# Sidekick-v02.net
KiCad netlist of a schematic drawn in EAGLE
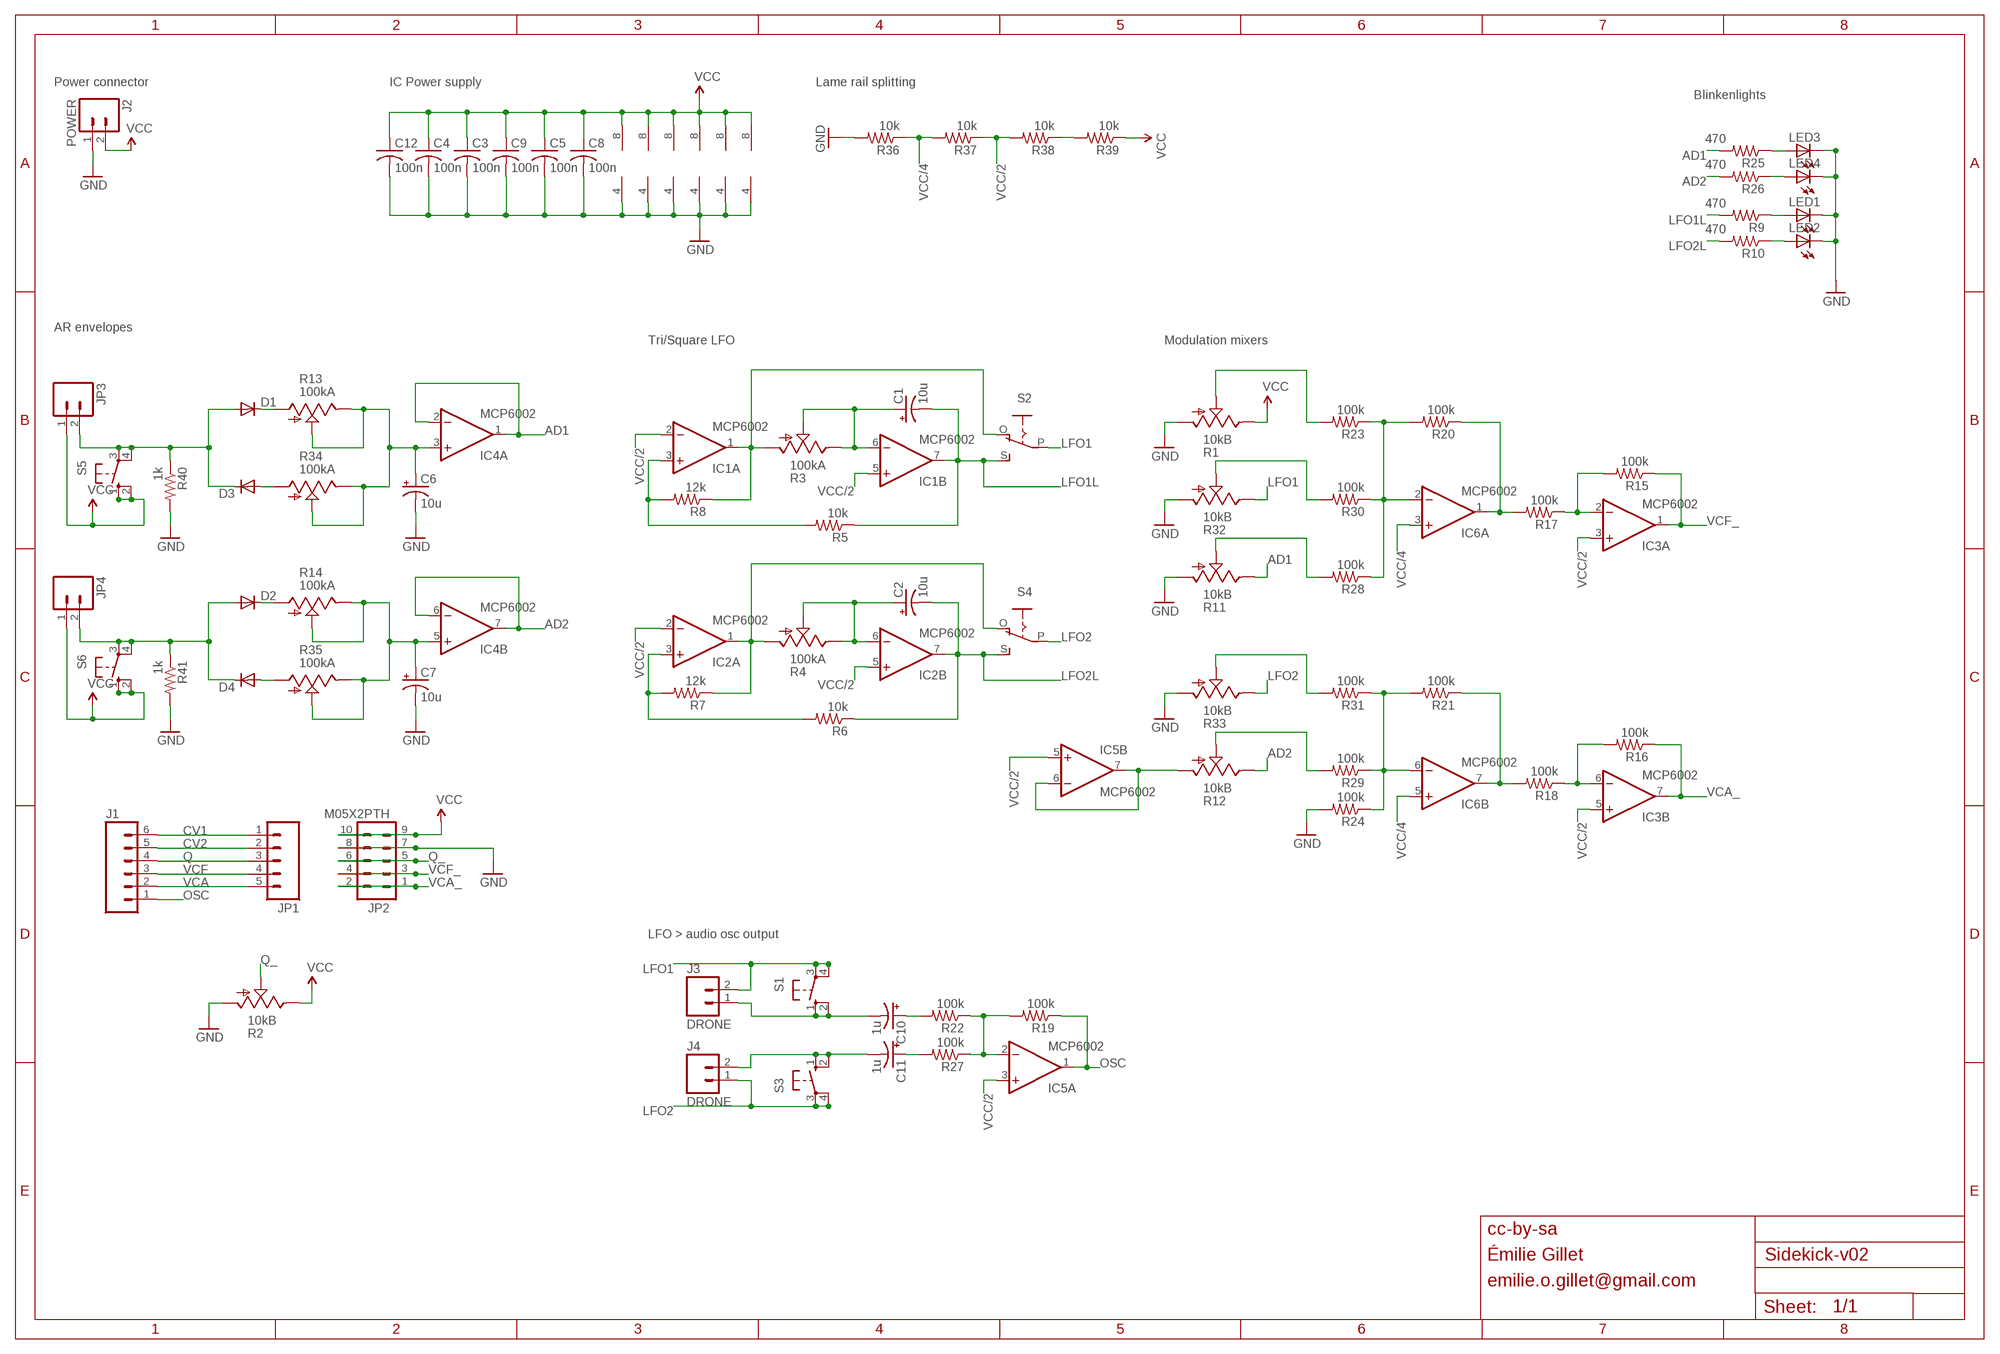
[diagram p0: schematic, sheet 1]

(export (version "E")
  (design (tool "Eeschema 10.0.6"))
  (components
    (comp (ref "C1")
      (value "10u")
      (footprint "eagle-import:E2,5-6")
      (libsource (lib "eagle-import") (part "CPOL-USE2.5-6"))
    )
    (comp (ref "C2")
      (value "10u")
      (footprint "eagle-import:E2,5-6")
      (libsource (lib "eagle-import") (part "CPOL-USE2.5-6"))
    )
    (comp (ref "C3")
      (value "100n")
      (footprint "eagle-import:C025-024X044")
      (libsource (lib "eagle-import") (part "C-US025-024X044"))
    )
    (comp (ref "C4")
      (value "100n")
      (footprint "eagle-import:C025-024X044")
      (libsource (lib "eagle-import") (part "C-US025-024X044"))
    )
    (comp (ref "C5")
      (value "100n")
      (footprint "eagle-import:C025-024X044")
      (libsource (lib "eagle-import") (part "C-US025-024X044"))
    )
    (comp (ref "C6")
      (value "10u")
      (footprint "eagle-import:E2,5-6")
      (libsource (lib "eagle-import") (part "CPOL-USE2.5-6"))
    )
    (comp (ref "C7")
      (value "10u")
      (footprint "eagle-import:E2,5-6")
      (libsource (lib "eagle-import") (part "CPOL-USE2.5-6"))
    )
    (comp (ref "C8")
      (value "100n")
      (footprint "eagle-import:C025-024X044")
      (libsource (lib "eagle-import") (part "C-US025-024X044"))
    )
    (comp (ref "C9")
      (value "100n")
      (footprint "eagle-import:C025-024X044")
      (libsource (lib "eagle-import") (part "C-US025-024X044"))
    )
    (comp (ref "C10")
      (value "1u")
      (footprint "eagle-import:E2,5-6")
      (libsource (lib "eagle-import") (part "CPOL-USE2.5-6"))
    )
    (comp (ref "C11")
      (value "1u")
      (footprint "eagle-import:E2,5-6")
      (libsource (lib "eagle-import") (part "CPOL-USE2.5-6"))
    )
    (comp (ref "C12")
      (value "100n")
      (footprint "eagle-import:C025-024X044")
      (libsource (lib "eagle-import") (part "C-US025-024X044"))
    )
    (comp (ref "D1")
      (value "DIODE-D-5")
      (footprint "eagle-import:D-5")
      (libsource (lib "eagle-import") (part "DIODE-D-5"))
    )
    (comp (ref "D2")
      (value "DIODE-D-5")
      (footprint "eagle-import:D-5")
      (libsource (lib "eagle-import") (part "DIODE-D-5"))
    )
    (comp (ref "D3")
      (value "DIODE-D-5")
      (footprint "eagle-import:D-5")
      (libsource (lib "eagle-import") (part "DIODE-D-5"))
    )
    (comp (ref "D4")
      (value "DIODE-D-5")
      (footprint "eagle-import:D-5")
      (libsource (lib "eagle-import") (part "DIODE-D-5"))
    )
    (comp (ref "IC1")
      (value "MCP6002")
      (footprint "eagle-import:DIL08")
      (libsource (lib "eagle-import") (part "TL082P"))
    )
    (comp (ref "IC2")
      (value "MCP6002")
      (footprint "eagle-import:DIL08")
      (libsource (lib "eagle-import") (part "TL082P"))
    )
    (comp (ref "IC3")
      (value "MCP6002")
      (footprint "eagle-import:DIL08")
      (libsource (lib "eagle-import") (part "TL082P"))
    )
    (comp (ref "IC4")
      (value "MCP6002")
      (footprint "eagle-import:DIL08")
      (libsource (lib "eagle-import") (part "TL082P"))
    )
    (comp (ref "IC5")
      (value "MCP6002")
      (footprint "eagle-import:DIL08")
      (libsource (lib "eagle-import") (part "TL082P"))
    )
    (comp (ref "IC6")
      (value "MCP6002")
      (footprint "eagle-import:DIL08")
      (libsource (lib "eagle-import") (part "TL082P"))
    )
    (comp (ref "J1")
      (value "M06SIP")
      (footprint "eagle-import:1X06")
      (libsource (lib "eagle-import") (part "M06SIP"))
    )
    (comp (ref "J2")
      (value "POWER")
      (footprint "eagle-import:1X02")
      (libsource (lib "eagle-import") (part "M02PTH"))
    )
    (comp (ref "J3")
      (value "DRONE")
      (footprint "eagle-import:1X02")
      (libsource (lib "eagle-import") (part "M02PTH"))
    )
    (comp (ref "J4")
      (value "DRONE")
      (footprint "eagle-import:1X02")
      (libsource (lib "eagle-import") (part "M02PTH"))
    )
    (comp (ref "JP1")
      (value "M05PTH")
      (footprint "eagle-import:1X05")
      (libsource (lib "eagle-import") (part "M05PTH"))
    )
    (comp (ref "JP2")
      (value "M05X2PTH")
      (footprint "eagle-import:AVR_ICSP")
      (libsource (lib "eagle-import") (part "M05X2PTH"))
    )
    (comp (ref "JP3")
      (value "M02")
      (footprint "eagle-import:1X02_LONGPADS")
      (libsource (lib "eagle-import") (part "M02"))
    )
    (comp (ref "JP4")
      (value "M02")
      (footprint "eagle-import:1X02_LONGPADS")
      (libsource (lib "eagle-import") (part "M02"))
    )
    (comp (ref "LED1")
      (value "LED3MM")
      (footprint "eagle-import:LED3MM")
      (libsource (lib "eagle-import") (part "LED3MM"))
    )
    (comp (ref "LED2")
      (value "LED3MM")
      (footprint "eagle-import:LED3MM")
      (libsource (lib "eagle-import") (part "LED3MM"))
    )
    (comp (ref "LED3")
      (value "LED3MM")
      (footprint "eagle-import:LED3MM")
      (libsource (lib "eagle-import") (part "LED3MM"))
    )
    (comp (ref "LED4")
      (value "LED3MM")
      (footprint "eagle-import:LED3MM")
      (libsource (lib "eagle-import") (part "LED3MM"))
    )
    (comp (ref "R1")
      (value "10kB")
      (footprint "eagle-import:ALPS_POT_SFE")
      (libsource (lib "eagle-import") (part "POT_US"))
    )
    (comp (ref "R2")
      (value "10kB")
      (footprint "eagle-import:ALPS_POT_SFE")
      (libsource (lib "eagle-import") (part "POT_US"))
    )
    (comp (ref "R3")
      (value "100kA")
      (footprint "eagle-import:ALPS_POT_SFE")
      (libsource (lib "eagle-import") (part "POT_US"))
    )
    (comp (ref "R4")
      (value "100kA")
      (footprint "eagle-import:ALPS_POT_SFE")
      (libsource (lib "eagle-import") (part "POT_US"))
    )
    (comp (ref "R5")
      (value "10k")
      (footprint "eagle-import:0204_7")
      (libsource (lib "eagle-import") (part "R-US_0204/7"))
    )
    (comp (ref "R6")
      (value "10k")
      (footprint "eagle-import:0204_7")
      (libsource (lib "eagle-import") (part "R-US_0204/7"))
    )
    (comp (ref "R7")
      (value "12k")
      (footprint "eagle-import:0204_7")
      (libsource (lib "eagle-import") (part "R-US_0204/7"))
    )
    (comp (ref "R8")
      (value "12k")
      (footprint "eagle-import:0204_7")
      (libsource (lib "eagle-import") (part "R-US_0204/7"))
    )
    (comp (ref "R9")
      (value "470")
      (footprint "eagle-import:0204_7")
      (libsource (lib "eagle-import") (part "R-US_0204/7"))
    )
    (comp (ref "R10")
      (value "470")
      (footprint "eagle-import:0204_7")
      (libsource (lib "eagle-import") (part "R-US_0204/7"))
    )
    (comp (ref "R11")
      (value "10kB")
      (footprint "eagle-import:ALPS_POT_SFE")
      (libsource (lib "eagle-import") (part "POT_US"))
    )
    (comp (ref "R12")
      (value "10kB")
      (footprint "eagle-import:ALPS_POT_SFE")
      (libsource (lib "eagle-import") (part "POT_US"))
    )
    (comp (ref "R13")
      (value "100kA")
      (footprint "eagle-import:ALPS_POT_SFE")
      (libsource (lib "eagle-import") (part "POT_US"))
    )
    (comp (ref "R14")
      (value "100kA")
      (footprint "eagle-import:ALPS_POT_SFE")
      (libsource (lib "eagle-import") (part "POT_US"))
    )
    (comp (ref "R15")
      (value "100k")
      (footprint "eagle-import:0204_7")
      (libsource (lib "eagle-import") (part "R-US_0204/7"))
    )
    (comp (ref "R16")
      (value "100k")
      (footprint "eagle-import:0204_7")
      (libsource (lib "eagle-import") (part "R-US_0204/7"))
    )
    (comp (ref "R17")
      (value "100k")
      (footprint "eagle-import:0204_7")
      (libsource (lib "eagle-import") (part "R-US_0204/7"))
    )
    (comp (ref "R18")
      (value "100k")
      (footprint "eagle-import:0204_7")
      (libsource (lib "eagle-import") (part "R-US_0204/7"))
    )
    (comp (ref "R19")
      (value "100k")
      (footprint "eagle-import:0204_7")
      (libsource (lib "eagle-import") (part "R-US_0204/7"))
    )
    (comp (ref "R20")
      (value "100k")
      (footprint "eagle-import:0204_7")
      (libsource (lib "eagle-import") (part "R-US_0204/7"))
    )
    (comp (ref "R21")
      (value "100k")
      (footprint "eagle-import:0204_7")
      (libsource (lib "eagle-import") (part "R-US_0204/7"))
    )
    (comp (ref "R22")
      (value "100k")
      (footprint "eagle-import:0204_7")
      (libsource (lib "eagle-import") (part "R-US_0204/7"))
    )
    (comp (ref "R23")
      (value "100k")
      (footprint "eagle-import:0204_7")
      (libsource (lib "eagle-import") (part "R-US_0204/7"))
    )
    (comp (ref "R24")
      (value "100k")
      (footprint "eagle-import:0204_7")
      (libsource (lib "eagle-import") (part "R-US_0204/7"))
    )
    (comp (ref "R25")
      (value "470")
      (footprint "eagle-import:0204_7")
      (libsource (lib "eagle-import") (part "R-US_0204/7"))
    )
    (comp (ref "R26")
      (value "470")
      (footprint "eagle-import:0204_7")
      (libsource (lib "eagle-import") (part "R-US_0204/7"))
    )
    (comp (ref "R27")
      (value "100k")
      (footprint "eagle-import:0204_7")
      (libsource (lib "eagle-import") (part "R-US_0204/7"))
    )
    (comp (ref "R28")
      (value "100k")
      (footprint "eagle-import:0204_7")
      (libsource (lib "eagle-import") (part "R-US_0204/7"))
    )
    (comp (ref "R29")
      (value "100k")
      (footprint "eagle-import:0204_7")
      (libsource (lib "eagle-import") (part "R-US_0204/7"))
    )
    (comp (ref "R30")
      (value "100k")
      (footprint "eagle-import:0204_7")
      (libsource (lib "eagle-import") (part "R-US_0204/7"))
    )
    (comp (ref "R31")
      (value "100k")
      (footprint "eagle-import:0204_7")
      (libsource (lib "eagle-import") (part "R-US_0204/7"))
    )
    (comp (ref "R32")
      (value "10kB")
      (footprint "eagle-import:ALPS_POT_SFE")
      (libsource (lib "eagle-import") (part "POT_US"))
    )
    (comp (ref "R33")
      (value "10kB")
      (footprint "eagle-import:ALPS_POT_SFE")
      (libsource (lib "eagle-import") (part "POT_US"))
    )
    (comp (ref "R34")
      (value "100kA")
      (footprint "eagle-import:ALPS_POT_SFE")
      (libsource (lib "eagle-import") (part "POT_US"))
    )
    (comp (ref "R35")
      (value "100kA")
      (footprint "eagle-import:ALPS_POT_SFE")
      (libsource (lib "eagle-import") (part "POT_US"))
    )
    (comp (ref "R36")
      (value "10k")
      (footprint "eagle-import:0204_7")
      (libsource (lib "eagle-import") (part "R-US_0204/7"))
    )
    (comp (ref "R37")
      (value "10k")
      (footprint "eagle-import:0204_7")
      (libsource (lib "eagle-import") (part "R-US_0204/7"))
    )
    (comp (ref "R38")
      (value "10k")
      (footprint "eagle-import:0204_7")
      (libsource (lib "eagle-import") (part "R-US_0204/7"))
    )
    (comp (ref "R39")
      (value "10k")
      (footprint "eagle-import:0204_7")
      (libsource (lib "eagle-import") (part "R-US_0204/7"))
    )
    (comp (ref "R40")
      (value "1k")
      (footprint "eagle-import:0204_7")
      (libsource (lib "eagle-import") (part "R-US_0204/7"))
    )
    (comp (ref "R41")
      (value "1k")
      (footprint "eagle-import:0204_7")
      (libsource (lib "eagle-import") (part "R-US_0204/7"))
    )
    (comp (ref "S1")
      (value "40-XX")
      (footprint "eagle-import:B3F-40XX")
      (libsource (lib "eagle-import") (part "40-XX"))
    )
    (comp (ref "S2")
      (value "EG1218S")
      (footprint "eagle-import:EG1218")
      (libsource (lib "eagle-import") (part "EG1218S"))
    )
    (comp (ref "S3")
      (value "40-XX")
      (footprint "eagle-import:B3F-40XX")
      (libsource (lib "eagle-import") (part "40-XX"))
    )
    (comp (ref "S4")
      (value "EG1218S")
      (footprint "eagle-import:EG1218")
      (libsource (lib "eagle-import") (part "EG1218S"))
    )
    (comp (ref "S5")
      (value "40-XX")
      (footprint "eagle-import:B3F-40XX")
      (libsource (lib "eagle-import") (part "40-XX"))
    )
    (comp (ref "S6")
      (value "40-XX")
      (footprint "eagle-import:B3F-40XX")
      (libsource (lib "eagle-import") (part "40-XX"))
    )
  )
  (nets
    (net (code "1") (name "/AD1") (class "Default")
      (node (ref "IC4") (pin "1") (pinfunction "OUT_1") (pintype "output"))
      (node (ref "IC4") (pin "2") (pinfunction "-IN_2") (pintype "input"))
      (node (ref "R11") (pin "P$1") (pinfunction "E_P$1") (pintype "passive"))
      (node (ref "R25") (pin "2") (pinfunction "2_2") (pintype "passive"))
    )
    (net (code "2") (name "/AD2") (class "Default")
      (node (ref "IC4") (pin "6") (pinfunction "-IN_6") (pintype "input"))
      (node (ref "IC4") (pin "7") (pinfunction "OUT_7") (pintype "output"))
      (node (ref "R12") (pin "P$1") (pinfunction "E_P$1") (pintype "passive"))
      (node (ref "R26") (pin "2") (pinfunction "2_2") (pintype "passive"))
    )
    (net (code "3") (name "/CV1") (class "Default")
      (node (ref "J1") (pin "6") (pinfunction "6_6") (pintype "passive"))
      (node (ref "JP1") (pin "1") (pinfunction "1_1") (pintype "passive"))
    )
    (net (code "4") (name "/CV2") (class "Default")
      (node (ref "J1") (pin "5") (pinfunction "5_5") (pintype "passive"))
      (node (ref "JP1") (pin "2") (pinfunction "2_2") (pintype "passive"))
    )
    (net (code "5") (name "/LFO1") (class "Default")
      (node (ref "J3") (pin "2") (pinfunction "2_2") (pintype "passive"))
      (node (ref "R32") (pin "P$1") (pinfunction "E_P$1") (pintype "passive"))
      (node (ref "S1") (pin "3") (pinfunction "P_3") (pintype "passive"))
      (node (ref "S1") (pin "4") (pinfunction "P1_4") (pintype "passive"))
      (node (ref "S2") (pin "P") (pinfunction "P_P") (pintype "passive"))
    )
    (net (code "6") (name "/LFO1L") (class "Default")
      (node (ref "C1") (pin "-") (pinfunction "-_-") (pintype "passive"))
      (node (ref "IC1") (pin "7") (pinfunction "OUT_7") (pintype "output"))
      (node (ref "R5") (pin "1") (pinfunction "1_1") (pintype "passive"))
      (node (ref "R9") (pin "2") (pinfunction "2_2") (pintype "passive"))
      (node (ref "S2") (pin "S") (pinfunction "S_S") (pintype "passive"))
    )
    (net (code "7") (name "/LFO2") (class "Default")
      (node (ref "J4") (pin "1") (pinfunction "1_1") (pintype "passive"))
      (node (ref "R33") (pin "P$1") (pinfunction "E_P$1") (pintype "passive"))
      (node (ref "S3") (pin "3") (pinfunction "P_3") (pintype "passive"))
      (node (ref "S3") (pin "4") (pinfunction "P1_4") (pintype "passive"))
      (node (ref "S4") (pin "P") (pinfunction "P_P") (pintype "passive"))
    )
    (net (code "8") (name "/LFO2L") (class "Default")
      (node (ref "C2") (pin "-") (pinfunction "-_-") (pintype "passive"))
      (node (ref "IC2") (pin "7") (pinfunction "OUT_7") (pintype "output"))
      (node (ref "R10") (pin "2") (pinfunction "2_2") (pintype "passive"))
      (node (ref "R6") (pin "1") (pinfunction "1_1") (pintype "passive"))
      (node (ref "S4") (pin "S") (pinfunction "S_S") (pintype "passive"))
    )
    (net (code "9") (name "/OSC") (class "Default")
      (node (ref "IC5") (pin "1") (pinfunction "OUT_1") (pintype "output"))
      (node (ref "J1") (pin "1") (pinfunction "1_1") (pintype "passive"))
      (node (ref "R19") (pin "1") (pinfunction "1_1") (pintype "passive"))
    )
    (net (code "10") (name "/Q") (class "Default")
      (node (ref "J1") (pin "4") (pinfunction "4_4") (pintype "passive"))
      (node (ref "JP1") (pin "3") (pinfunction "3_3") (pintype "passive"))
    )
    (net (code "11") (name "/Q_") (class "Default")
      (node (ref "JP2") (pin "5") (pinfunction "5_5") (pintype "passive"))
      (node (ref "JP2") (pin "6") (pinfunction "6_6") (pintype "passive"))
      (node (ref "R2") (pin "P$2") (pinfunction "S_P$2") (pintype "passive"))
    )
    (net (code "12") (name "/VCA") (class "Default")
      (node (ref "J1") (pin "2") (pinfunction "2_2") (pintype "passive"))
      (node (ref "JP1") (pin "5") (pinfunction "5_5") (pintype "passive"))
    )
    (net (code "13") (name "/VCA_") (class "Default")
      (node (ref "IC3") (pin "7") (pinfunction "OUT_7") (pintype "output"))
      (node (ref "JP2") (pin "1") (pinfunction "1_1") (pintype "passive"))
      (node (ref "JP2") (pin "2") (pinfunction "2_2") (pintype "passive"))
      (node (ref "R16") (pin "1") (pinfunction "1_1") (pintype "passive"))
    )
    (net (code "14") (name "/VCC{slash}2") (class "Default")
      (node (ref "IC1") (pin "2") (pinfunction "-IN_2") (pintype "input"))
      (node (ref "IC1") (pin "5") (pinfunction "+IN_5") (pintype "input"))
      (node (ref "IC2") (pin "2") (pinfunction "-IN_2") (pintype "input"))
      (node (ref "IC2") (pin "5") (pinfunction "+IN_5") (pintype "input"))
      (node (ref "IC3") (pin "3") (pinfunction "+IN_3") (pintype "input"))
      (node (ref "IC3") (pin "5") (pinfunction "+IN_5") (pintype "input"))
      (node (ref "IC5") (pin "3") (pinfunction "+IN_3") (pintype "input"))
      (node (ref "IC5") (pin "5") (pinfunction "+IN_5") (pintype "input"))
      (node (ref "R37") (pin "1") (pinfunction "1_1") (pintype "passive"))
      (node (ref "R38") (pin "2") (pinfunction "2_2") (pintype "passive"))
    )
    (net (code "15") (name "/VCC{slash}4") (class "Default")
      (node (ref "IC6") (pin "3") (pinfunction "+IN_3") (pintype "input"))
      (node (ref "IC6") (pin "5") (pinfunction "+IN_5") (pintype "input"))
      (node (ref "R36") (pin "1") (pinfunction "1_1") (pintype "passive"))
      (node (ref "R37") (pin "2") (pinfunction "2_2") (pintype "passive"))
    )
    (net (code "16") (name "/VCF") (class "Default")
      (node (ref "J1") (pin "3") (pinfunction "3_3") (pintype "passive"))
      (node (ref "JP1") (pin "4") (pinfunction "4_4") (pintype "passive"))
    )
    (net (code "17") (name "/VCF_") (class "Default")
      (node (ref "IC3") (pin "1") (pinfunction "OUT_1") (pintype "output"))
      (node (ref "JP2") (pin "3") (pinfunction "3_3") (pintype "passive"))
      (node (ref "JP2") (pin "4") (pinfunction "4_4") (pintype "passive"))
      (node (ref "R15") (pin "1") (pinfunction "1_1") (pintype "passive"))
    )
    (net (code "18") (name "GND") (class "Default")
      (node (ref "C12") (pin "2") (pinfunction "2_2") (pintype "passive"))
      (node (ref "C3") (pin "2") (pinfunction "2_2") (pintype "passive"))
      (node (ref "C4") (pin "2") (pinfunction "2_2") (pintype "passive"))
      (node (ref "C5") (pin "2") (pinfunction "2_2") (pintype "passive"))
      (node (ref "C6") (pin "-") (pinfunction "-_-") (pintype "passive"))
      (node (ref "C7") (pin "-") (pinfunction "-_-") (pintype "passive"))
      (node (ref "C8") (pin "2") (pinfunction "2_2") (pintype "passive"))
      (node (ref "C9") (pin "2") (pinfunction "2_2") (pintype "passive"))
      (node (ref "IC1") (pin "4") (pinfunction "V-_4") (pintype "power_in"))
      (node (ref "IC2") (pin "4") (pinfunction "V-_4") (pintype "power_in"))
      (node (ref "IC3") (pin "4") (pinfunction "V-_4") (pintype "power_in"))
      (node (ref "IC4") (pin "4") (pinfunction "V-_4") (pintype "power_in"))
      (node (ref "IC5") (pin "4") (pinfunction "V-_4") (pintype "power_in"))
      (node (ref "IC6") (pin "4") (pinfunction "V-_4") (pintype "power_in"))
      (node (ref "J2") (pin "1") (pinfunction "1_1") (pintype "passive"))
      (node (ref "JP2") (pin "7") (pinfunction "7_7") (pintype "passive"))
      (node (ref "JP2") (pin "8") (pinfunction "8_8") (pintype "passive"))
      (node (ref "LED1") (pin "K") (pinfunction "C_K") (pintype "passive"))
      (node (ref "LED2") (pin "K") (pinfunction "C_K") (pintype "passive"))
      (node (ref "LED3") (pin "K") (pinfunction "C_K") (pintype "passive"))
      (node (ref "LED4") (pin "K") (pinfunction "C_K") (pintype "passive"))
      (node (ref "R1") (pin "P$3") (pinfunction "A_P$3") (pintype "passive"))
      (node (ref "R11") (pin "P$3") (pinfunction "A_P$3") (pintype "passive"))
      (node (ref "R2") (pin "P$3") (pinfunction "A_P$3") (pintype "passive"))
      (node (ref "R24") (pin "2") (pinfunction "2_2") (pintype "passive"))
      (node (ref "R32") (pin "P$3") (pinfunction "A_P$3") (pintype "passive"))
      (node (ref "R33") (pin "P$3") (pinfunction "A_P$3") (pintype "passive"))
      (node (ref "R36") (pin "2") (pinfunction "2_2") (pintype "passive"))
      (node (ref "R40") (pin "2") (pinfunction "2_2") (pintype "passive"))
      (node (ref "R41") (pin "2") (pinfunction "2_2") (pintype "passive"))
    )
    (net (code "19") (name "Net-(C10-Pad+)") (class "Default")
      (node (ref "C10") (pin "+") (pinfunction "+_+") (pintype "passive"))
      (node (ref "R22") (pin "2") (pinfunction "2_2") (pintype "passive"))
    )
    (net (code "20") (name "Net-(C11-Pad+)") (class "Default")
      (node (ref "C11") (pin "+") (pinfunction "+_+") (pintype "passive"))
      (node (ref "R27") (pin "2") (pinfunction "2_2") (pintype "passive"))
    )
    (net (code "21") (name "Net-(IC1A-+IN)") (class "Default")
      (node (ref "IC1") (pin "3") (pinfunction "+IN_3") (pintype "input"))
      (node (ref "R5") (pin "2") (pinfunction "2_2") (pintype "passive"))
      (node (ref "R8") (pin "2") (pinfunction "2_2") (pintype "passive"))
    )
    (net (code "22") (name "Net-(IC1A-OUT)") (class "Default")
      (node (ref "IC1") (pin "1") (pinfunction "OUT_1") (pintype "output"))
      (node (ref "R3") (pin "P$3") (pinfunction "A_P$3") (pintype "passive"))
      (node (ref "R8") (pin "1") (pinfunction "1_1") (pintype "passive"))
      (node (ref "S2") (pin "O") (pinfunction "O_O") (pintype "passive"))
    )
    (net (code "23") (name "Net-(IC1B--IN)") (class "Default")
      (node (ref "C1") (pin "+") (pinfunction "+_+") (pintype "passive"))
      (node (ref "IC1") (pin "6") (pinfunction "-IN_6") (pintype "input"))
      (node (ref "R3") (pin "P$1") (pinfunction "E_P$1") (pintype "passive"))
      (node (ref "R3") (pin "P$2") (pinfunction "S_P$2") (pintype "passive"))
    )
    (net (code "24") (name "Net-(IC2A-+IN)") (class "Default")
      (node (ref "IC2") (pin "3") (pinfunction "+IN_3") (pintype "input"))
      (node (ref "R6") (pin "2") (pinfunction "2_2") (pintype "passive"))
      (node (ref "R7") (pin "2") (pinfunction "2_2") (pintype "passive"))
    )
    (net (code "25") (name "Net-(IC2A-OUT)") (class "Default")
      (node (ref "IC2") (pin "1") (pinfunction "OUT_1") (pintype "output"))
      (node (ref "R4") (pin "P$3") (pinfunction "A_P$3") (pintype "passive"))
      (node (ref "R7") (pin "1") (pinfunction "1_1") (pintype "passive"))
      (node (ref "S4") (pin "O") (pinfunction "O_O") (pintype "passive"))
    )
    (net (code "26") (name "Net-(IC2B--IN)") (class "Default")
      (node (ref "C2") (pin "+") (pinfunction "+_+") (pintype "passive"))
      (node (ref "IC2") (pin "6") (pinfunction "-IN_6") (pintype "input"))
      (node (ref "R4") (pin "P$1") (pinfunction "E_P$1") (pintype "passive"))
      (node (ref "R4") (pin "P$2") (pinfunction "S_P$2") (pintype "passive"))
    )
    (net (code "27") (name "Net-(IC3A--IN)") (class "Default")
      (node (ref "IC3") (pin "2") (pinfunction "-IN_2") (pintype "input"))
      (node (ref "R15") (pin "2") (pinfunction "2_2") (pintype "passive"))
      (node (ref "R17") (pin "1") (pinfunction "1_1") (pintype "passive"))
    )
    (net (code "28") (name "Net-(IC3B--IN)") (class "Default")
      (node (ref "IC3") (pin "6") (pinfunction "-IN_6") (pintype "input"))
      (node (ref "R16") (pin "2") (pinfunction "2_2") (pintype "passive"))
      (node (ref "R18") (pin "1") (pinfunction "1_1") (pintype "passive"))
    )
    (net (code "29") (name "Net-(IC4A-+IN)") (class "Default")
      (node (ref "C6") (pin "+") (pinfunction "+_+") (pintype "passive"))
      (node (ref "IC4") (pin "3") (pinfunction "+IN_3") (pintype "input"))
      (node (ref "R13") (pin "P$1") (pinfunction "E_P$1") (pintype "passive"))
      (node (ref "R13") (pin "P$2") (pinfunction "S_P$2") (pintype "passive"))
      (node (ref "R34") (pin "P$1") (pinfunction "E_P$1") (pintype "passive"))
      (node (ref "R34") (pin "P$2") (pinfunction "S_P$2") (pintype "passive"))
    )
    (net (code "30") (name "Net-(IC4B-+IN)") (class "Default")
      (node (ref "C7") (pin "+") (pinfunction "+_+") (pintype "passive"))
      (node (ref "IC4") (pin "5") (pinfunction "+IN_5") (pintype "input"))
      (node (ref "R14") (pin "P$1") (pinfunction "E_P$1") (pintype "passive"))
      (node (ref "R14") (pin "P$2") (pinfunction "S_P$2") (pintype "passive"))
      (node (ref "R35") (pin "P$1") (pinfunction "E_P$1") (pintype "passive"))
      (node (ref "R35") (pin "P$2") (pinfunction "S_P$2") (pintype "passive"))
    )
    (net (code "31") (name "Net-(IC5A--IN)") (class "Default")
      (node (ref "IC5") (pin "2") (pinfunction "-IN_2") (pintype "input"))
      (node (ref "R19") (pin "2") (pinfunction "2_2") (pintype "passive"))
      (node (ref "R22") (pin "1") (pinfunction "1_1") (pintype "passive"))
      (node (ref "R27") (pin "1") (pinfunction "1_1") (pintype "passive"))
    )
    (net (code "32") (name "Net-(IC5B--IN)") (class "Default")
      (node (ref "IC5") (pin "6") (pinfunction "-IN_6") (pintype "input"))
      (node (ref "IC5") (pin "7") (pinfunction "OUT_7") (pintype "output"))
      (node (ref "R12") (pin "P$3") (pinfunction "A_P$3") (pintype "passive"))
    )
    (net (code "33") (name "Net-(IC6A--IN)") (class "Default")
      (node (ref "IC6") (pin "2") (pinfunction "-IN_2") (pintype "input"))
      (node (ref "R20") (pin "2") (pinfunction "2_2") (pintype "passive"))
      (node (ref "R23") (pin "1") (pinfunction "1_1") (pintype "passive"))
      (node (ref "R28") (pin "1") (pinfunction "1_1") (pintype "passive"))
      (node (ref "R30") (pin "1") (pinfunction "1_1") (pintype "passive"))
    )
    (net (code "34") (name "Net-(IC6A-OUT)") (class "Default")
      (node (ref "IC6") (pin "1") (pinfunction "OUT_1") (pintype "output"))
      (node (ref "R17") (pin "2") (pinfunction "2_2") (pintype "passive"))
      (node (ref "R20") (pin "1") (pinfunction "1_1") (pintype "passive"))
    )
    (net (code "35") (name "Net-(IC6B--IN)") (class "Default")
      (node (ref "IC6") (pin "6") (pinfunction "-IN_6") (pintype "input"))
      (node (ref "R21") (pin "2") (pinfunction "2_2") (pintype "passive"))
      (node (ref "R24") (pin "1") (pinfunction "1_1") (pintype "passive"))
      (node (ref "R29") (pin "1") (pinfunction "1_1") (pintype "passive"))
      (node (ref "R31") (pin "1") (pinfunction "1_1") (pintype "passive"))
    )
    (net (code "36") (name "Net-(IC6B-OUT)") (class "Default")
      (node (ref "IC6") (pin "7") (pinfunction "OUT_7") (pintype "output"))
      (node (ref "R18") (pin "2") (pinfunction "2_2") (pintype "passive"))
      (node (ref "R21") (pin "1") (pinfunction "1_1") (pintype "passive"))
    )
    (net (code "37") (name "Net-(LED1-PadA)") (class "Default")
      (node (ref "LED1") (pin "A") (pinfunction "A_A") (pintype "passive"))
      (node (ref "R9") (pin "1") (pinfunction "1_1") (pintype "passive"))
    )
    (net (code "38") (name "Net-(LED2-PadA)") (class "Default")
      (node (ref "LED2") (pin "A") (pinfunction "A_A") (pintype "passive"))
      (node (ref "R10") (pin "1") (pinfunction "1_1") (pintype "passive"))
    )
    (net (code "39") (name "Net-(LED3-PadA)") (class "Default")
      (node (ref "LED3") (pin "A") (pinfunction "A_A") (pintype "passive"))
      (node (ref "R25") (pin "1") (pinfunction "1_1") (pintype "passive"))
    )
    (net (code "40") (name "Net-(LED4-PadA)") (class "Default")
      (node (ref "LED4") (pin "A") (pinfunction "A_A") (pintype "passive"))
      (node (ref "R26") (pin "1") (pinfunction "1_1") (pintype "passive"))
    )
    (net (code "41") (name "Net-(R1-S)") (class "Default")
      (node (ref "R1") (pin "P$2") (pinfunction "S_P$2") (pintype "passive"))
      (node (ref "R23") (pin "2") (pinfunction "2_2") (pintype "passive"))
    )
    (net (code "42") (name "Net-(R11-S)") (class "Default")
      (node (ref "R11") (pin "P$2") (pinfunction "S_P$2") (pintype "passive"))
      (node (ref "R28") (pin "2") (pinfunction "2_2") (pintype "passive"))
    )
    (net (code "43") (name "Net-(R12-S)") (class "Default")
      (node (ref "R12") (pin "P$2") (pinfunction "S_P$2") (pintype "passive"))
      (node (ref "R29") (pin "2") (pinfunction "2_2") (pintype "passive"))
    )
    (net (code "44") (name "Net-(R13-A)") (class "Default")
      (node (ref "D1") (pin "C") (pinfunction "C_C") (pintype "passive"))
      (node (ref "R13") (pin "P$3") (pinfunction "A_P$3") (pintype "passive"))
    )
    (net (code "45") (name "Net-(R14-A)") (class "Default")
      (node (ref "D2") (pin "C") (pinfunction "C_C") (pintype "passive"))
      (node (ref "R14") (pin "P$3") (pinfunction "A_P$3") (pintype "passive"))
    )
    (net (code "46") (name "Net-(R32-S)") (class "Default")
      (node (ref "R30") (pin "2") (pinfunction "2_2") (pintype "passive"))
      (node (ref "R32") (pin "P$2") (pinfunction "S_P$2") (pintype "passive"))
    )
    (net (code "47") (name "Net-(R33-S)") (class "Default")
      (node (ref "R31") (pin "2") (pinfunction "2_2") (pintype "passive"))
      (node (ref "R33") (pin "P$2") (pinfunction "S_P$2") (pintype "passive"))
    )
    (net (code "48") (name "Net-(R34-A)") (class "Default")
      (node (ref "D3") (pin "A") (pinfunction "A_A") (pintype "passive"))
      (node (ref "R34") (pin "P$3") (pinfunction "A_P$3") (pintype "passive"))
    )
    (net (code "49") (name "Net-(R35-A)") (class "Default")
      (node (ref "D4") (pin "A") (pinfunction "A_A") (pintype "passive"))
      (node (ref "R35") (pin "P$3") (pinfunction "A_P$3") (pintype "passive"))
    )
    (net (code "50") (name "Net-(R38-Pad1)") (class "Default")
      (node (ref "R38") (pin "1") (pinfunction "1_1") (pintype "passive"))
      (node (ref "R39") (pin "2") (pinfunction "2_2") (pintype "passive"))
    )
    (net (code "51") (name "Net-(S1-S)") (class "Default")
      (node (ref "C10") (pin "-") (pinfunction "-_-") (pintype "passive"))
      (node (ref "J3") (pin "1") (pinfunction "1_1") (pintype "passive"))
      (node (ref "S1") (pin "1") (pinfunction "S_1") (pintype "passive"))
      (node (ref "S1") (pin "2") (pinfunction "S1_2") (pintype "passive"))
    )
    (net (code "52") (name "Net-(S3-S)") (class "Default")
      (node (ref "C11") (pin "-") (pinfunction "-_-") (pintype "passive"))
      (node (ref "J4") (pin "2") (pinfunction "2_2") (pintype "passive"))
      (node (ref "S3") (pin "1") (pinfunction "S_1") (pintype "passive"))
      (node (ref "S3") (pin "2") (pinfunction "S1_2") (pintype "passive"))
    )
    (net (code "53") (name "Net-(S5-P)") (class "Default")
      (node (ref "D1") (pin "A") (pinfunction "A_A") (pintype "passive"))
      (node (ref "D3") (pin "C") (pinfunction "C_C") (pintype "passive"))
      (node (ref "JP3") (pin "2") (pinfunction "2_2") (pintype "passive"))
      (node (ref "R40") (pin "1") (pinfunction "1_1") (pintype "passive"))
      (node (ref "S5") (pin "3") (pinfunction "P_3") (pintype "passive"))
      (node (ref "S5") (pin "4") (pinfunction "P1_4") (pintype "passive"))
    )
    (net (code "54") (name "Net-(S6-P)") (class "Default")
      (node (ref "D2") (pin "A") (pinfunction "A_A") (pintype "passive"))
      (node (ref "D4") (pin "C") (pinfunction "C_C") (pintype "passive"))
      (node (ref "JP4") (pin "2") (pinfunction "2_2") (pintype "passive"))
      (node (ref "R41") (pin "1") (pinfunction "1_1") (pintype "passive"))
      (node (ref "S6") (pin "3") (pinfunction "P_3") (pintype "passive"))
      (node (ref "S6") (pin "4") (pinfunction "P1_4") (pintype "passive"))
    )
    (net (code "55") (name "VCC") (class "Default")
      (node (ref "C12") (pin "1") (pinfunction "1_1") (pintype "passive"))
      (node (ref "C3") (pin "1") (pinfunction "1_1") (pintype "passive"))
      (node (ref "C4") (pin "1") (pinfunction "1_1") (pintype "passive"))
      (node (ref "C5") (pin "1") (pinfunction "1_1") (pintype "passive"))
      (node (ref "C8") (pin "1") (pinfunction "1_1") (pintype "passive"))
      (node (ref "C9") (pin "1") (pinfunction "1_1") (pintype "passive"))
      (node (ref "IC1") (pin "8") (pinfunction "V+_8") (pintype "power_in"))
      (node (ref "IC2") (pin "8") (pinfunction "V+_8") (pintype "power_in"))
      (node (ref "IC3") (pin "8") (pinfunction "V+_8") (pintype "power_in"))
      (node (ref "IC4") (pin "8") (pinfunction "V+_8") (pintype "power_in"))
      (node (ref "IC5") (pin "8") (pinfunction "V+_8") (pintype "power_in"))
      (node (ref "IC6") (pin "8") (pinfunction "V+_8") (pintype "power_in"))
      (node (ref "J2") (pin "2") (pinfunction "2_2") (pintype "passive"))
      (node (ref "JP2") (pin "10") (pinfunction "10_10") (pintype "passive"))
      (node (ref "JP2") (pin "9") (pinfunction "9_9") (pintype "passive"))
      (node (ref "JP3") (pin "1") (pinfunction "1_1") (pintype "passive"))
      (node (ref "JP4") (pin "1") (pinfunction "1_1") (pintype "passive"))
      (node (ref "R1") (pin "P$1") (pinfunction "E_P$1") (pintype "passive"))
      (node (ref "R2") (pin "P$1") (pinfunction "E_P$1") (pintype "passive"))
      (node (ref "R39") (pin "1") (pinfunction "1_1") (pintype "passive"))
      (node (ref "S5") (pin "1") (pinfunction "S_1") (pintype "passive"))
      (node (ref "S5") (pin "2") (pinfunction "S1_2") (pintype "passive"))
      (node (ref "S6") (pin "1") (pinfunction "S_1") (pintype "passive"))
      (node (ref "S6") (pin "2") (pinfunction "S1_2") (pintype "passive"))
    )
  )
)
